# DLY_1_0.net
KiCad netlist of a schematic drawn in EAGLE
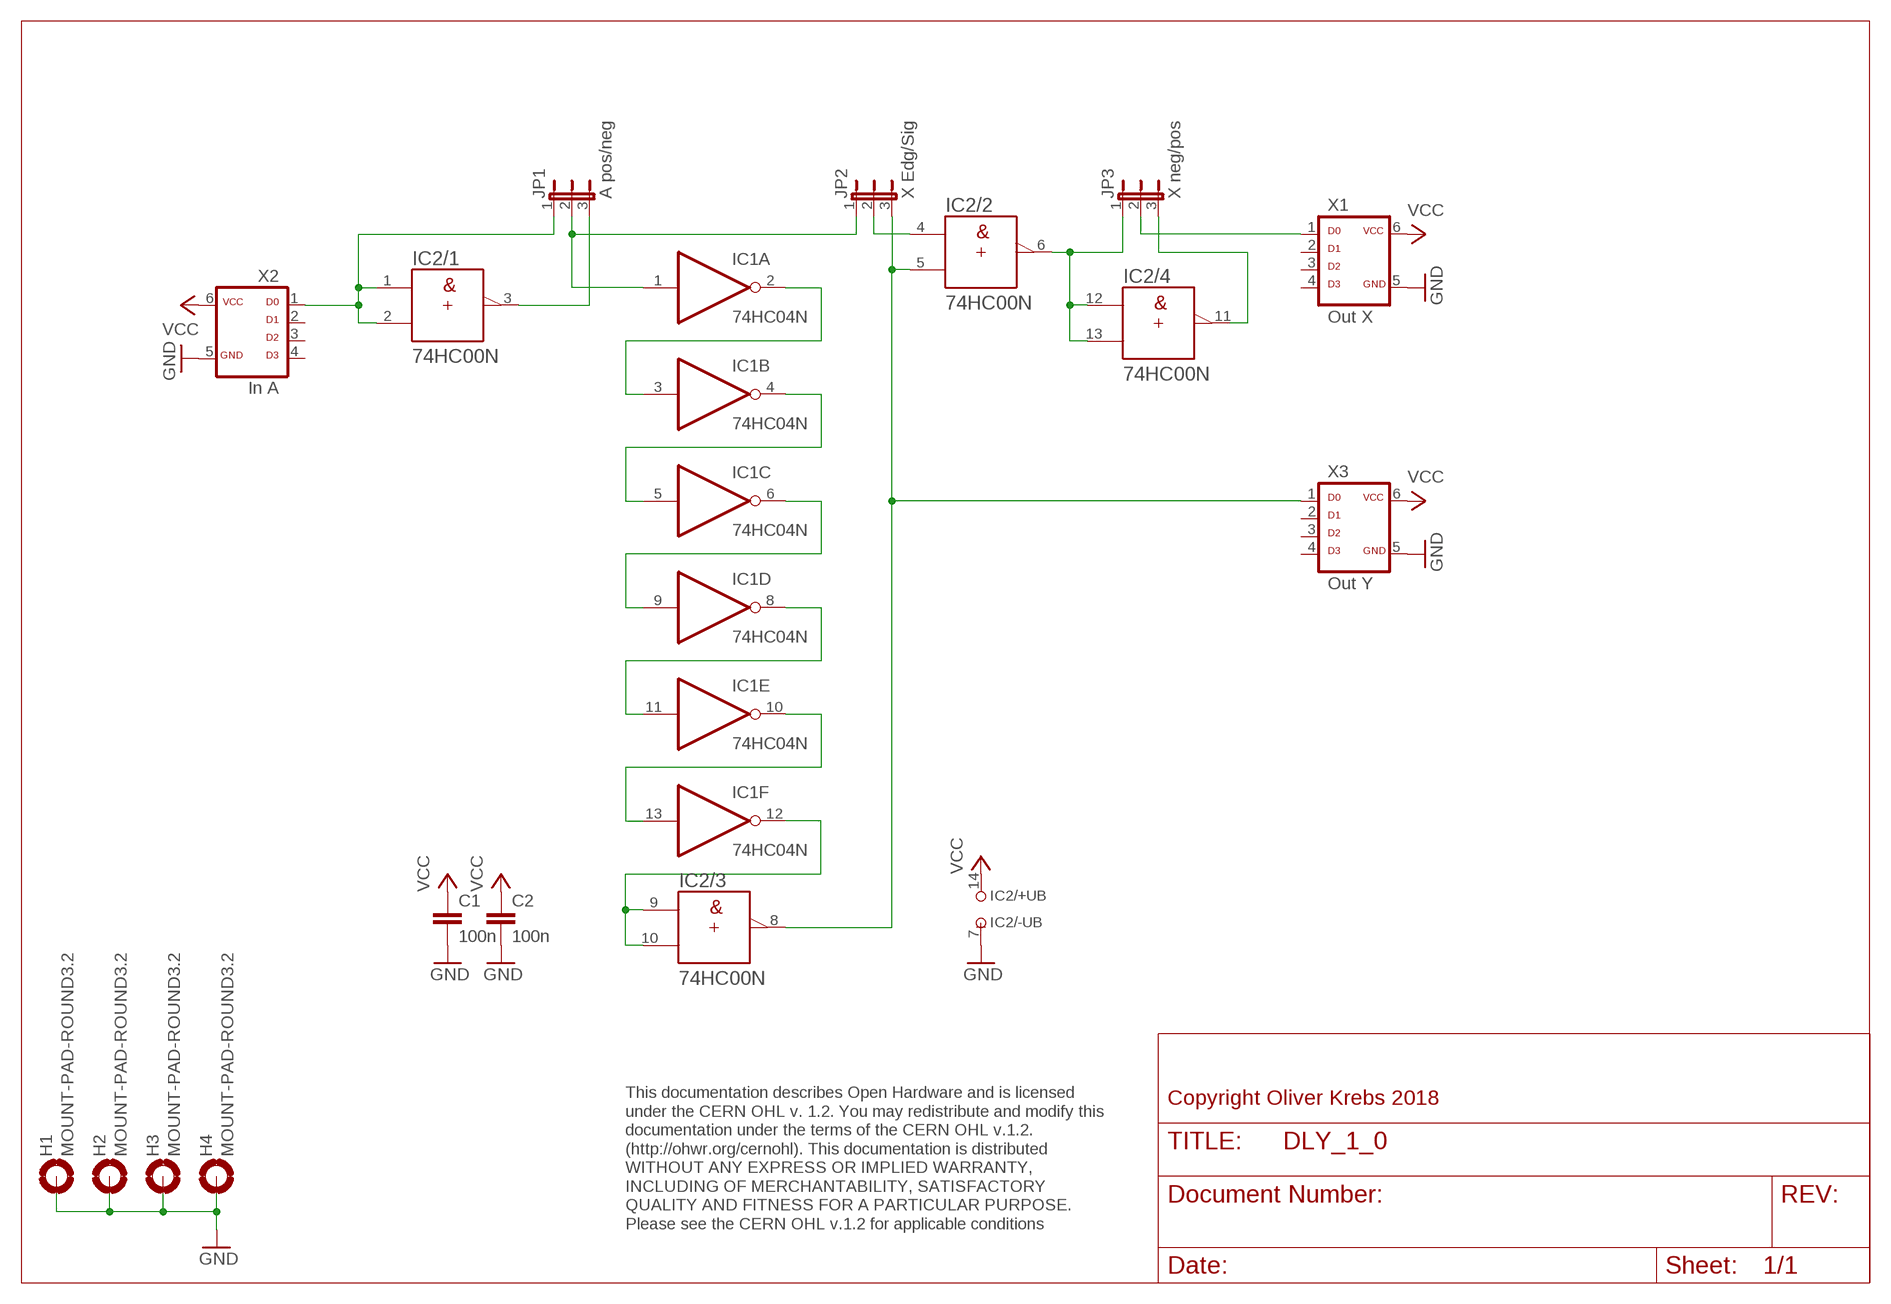
[diagram p0: schematic, sheet 1]

(export (version "E")
  (design (tool "Eeschema 10.0.6"))
  (components
    (comp (ref "C1")
      (value "100n")
      (footprint "eagle-import:C050-025X075")
      (libsource (lib "eagle-import") (part "C-EU050-025X075"))
    )
    (comp (ref "C2")
      (value "100n")
      (footprint "eagle-import:C050-025X075")
      (libsource (lib "eagle-import") (part "C-EU050-025X075"))
    )
    (comp (ref "H1")
      (value "MOUNT-PAD-ROUND3.2")
      (footprint "eagle-import:3,2-PAD")
      (libsource (lib "eagle-import") (part "MOUNT-PAD-ROUND3.2"))
    )
    (comp (ref "H2")
      (value "MOUNT-PAD-ROUND3.2")
      (footprint "eagle-import:3,2-PAD")
      (libsource (lib "eagle-import") (part "MOUNT-PAD-ROUND3.2"))
    )
    (comp (ref "H3")
      (value "MOUNT-PAD-ROUND3.2")
      (footprint "eagle-import:3,2-PAD")
      (libsource (lib "eagle-import") (part "MOUNT-PAD-ROUND3.2"))
    )
    (comp (ref "H4")
      (value "MOUNT-PAD-ROUND3.2")
      (footprint "eagle-import:3,2-PAD")
      (libsource (lib "eagle-import") (part "MOUNT-PAD-ROUND3.2"))
    )
    (comp (ref "IC1")
      (value "74HC04N")
      (footprint "eagle-import:DIL14")
      (libsource (lib "eagle-import") (part "7404NHC"))
    )
    (comp (ref "IC2")
      (value "74HC00N")
      (footprint "eagle-import:DIL14")
      (libsource (lib "eagle-import") (part "7400NHC"))
    )
    (comp (ref "JP1")
      (value "A pos/neg")
      (footprint "eagle-import:JP2")
      (libsource (lib "eagle-import") (part "JP2EJP2"))
    )
    (comp (ref "JP2")
      (value "X Edg/Sig")
      (footprint "eagle-import:JP2")
      (libsource (lib "eagle-import") (part "JP2EJP2"))
    )
    (comp (ref "JP3")
      (value "X neg/pos")
      (footprint "eagle-import:JP2")
      (libsource (lib "eagle-import") (part "JP2EJP2"))
    )
    (comp (ref "X1")
      (value "Out X")
      (footprint "eagle-import:ML-6")
      (libsource (lib "eagle-import") (part "ML6D"))
    )
    (comp (ref "X2")
      (value "In A")
      (footprint "eagle-import:ML-6")
      (libsource (lib "eagle-import") (part "ML6D"))
    )
    (comp (ref "X3")
      (value "Out Y")
      (footprint "eagle-import:ML-6")
      (libsource (lib "eagle-import") (part "ML6D"))
    )
  )
  (nets
    (net (code "1") (name "GND") (class "Default")
      (node (ref "C1") (pin "2") (pinfunction "2_2") (pintype "passive"))
      (node (ref "C2") (pin "2") (pinfunction "2_2") (pintype "passive"))
      (node (ref "H1") (pin "B3,2") (pinfunction "MOUNT_B3,2") (pintype "passive"))
      (node (ref "H2") (pin "B3,2") (pinfunction "MOUNT_B3,2") (pintype "passive"))
      (node (ref "H3") (pin "B3,2") (pinfunction "MOUNT_B3,2") (pintype "passive"))
      (node (ref "H4") (pin "B3,2") (pinfunction "MOUNT_B3,2") (pintype "passive"))
      (node (ref "IC2") (pin "7") (pinfunction "-UB_7") (pintype "power_in"))
      (node (ref "X1") (pin "5") (pinfunction "5_5") (pintype "passive"))
      (node (ref "X2") (pin "5") (pinfunction "5_5") (pintype "passive"))
      (node (ref "X3") (pin "5") (pinfunction "5_5") (pintype "passive"))
    )
    (net (code "2") (name "Net-(IC1A-I)") (class "Default")
      (node (ref "IC1") (pin "1") (pinfunction "I_1") (pintype "input"))
      (node (ref "JP1") (pin "2") (pinfunction "2_2") (pintype "passive"))
      (node (ref "JP2") (pin "1") (pinfunction "1_1") (pintype "passive"))
    )
    (net (code "3") (name "Net-(IC1A-O)") (class "Default")
      (node (ref "IC1") (pin "2") (pinfunction "O_2") (pintype "output"))
      (node (ref "IC1") (pin "3") (pinfunction "I_3") (pintype "input"))
    )
    (net (code "4") (name "Net-(IC1B-O)") (class "Default")
      (node (ref "IC1") (pin "4") (pinfunction "O_4") (pintype "output"))
      (node (ref "IC1") (pin "5") (pinfunction "I_5") (pintype "input"))
    )
    (net (code "5") (name "Net-(IC1C-O)") (class "Default")
      (node (ref "IC1") (pin "6") (pinfunction "O_6") (pintype "output"))
      (node (ref "IC1") (pin "9") (pinfunction "I_9") (pintype "input"))
    )
    (net (code "6") (name "Net-(IC1D-O)") (class "Default")
      (node (ref "IC1") (pin "11") (pinfunction "I_11") (pintype "input"))
      (node (ref "IC1") (pin "8") (pinfunction "O_8") (pintype "output"))
    )
    (net (code "7") (name "Net-(IC1E-O)") (class "Default")
      (node (ref "IC1") (pin "10") (pinfunction "O_10") (pintype "output"))
      (node (ref "IC1") (pin "13") (pinfunction "I_13") (pintype "input"))
    )
    (net (code "8") (name "Net-(IC1F-O)") (class "Default")
      (node (ref "IC1") (pin "12") (pinfunction "O_12") (pintype "output"))
      (node (ref "IC2") (pin "10") (pinfunction "B_10") (pintype "input"))
      (node (ref "IC2") (pin "9") (pinfunction "A_9") (pintype "input"))
    )
    (net (code "9") (name "Net-(IC2C-A)") (class "Default")
      (node (ref "IC2") (pin "1") (pinfunction "A_1") (pintype "input"))
      (node (ref "IC2") (pin "2") (pinfunction "B_2") (pintype "input"))
      (node (ref "JP1") (pin "1") (pinfunction "1_1") (pintype "passive"))
      (node (ref "X2") (pin "1") (pinfunction "1_1") (pintype "passive"))
    )
    (net (code "10") (name "Net-(IC2C-Y)") (class "Default")
      (node (ref "IC2") (pin "3") (pinfunction "Y_3") (pintype "output"))
      (node (ref "JP1") (pin "3") (pinfunction "3_3") (pintype "passive"))
    )
    (net (code "11") (name "Net-(IC2D-A)") (class "Default")
      (node (ref "IC2") (pin "4") (pinfunction "A_4") (pintype "input"))
      (node (ref "JP2") (pin "2") (pinfunction "2_2") (pintype "passive"))
    )
    (net (code "12") (name "Net-(IC2D-B)") (class "Default")
      (node (ref "IC2") (pin "5") (pinfunction "B_5") (pintype "input"))
      (node (ref "IC2") (pin "8") (pinfunction "Y_8") (pintype "output"))
      (node (ref "JP2") (pin "3") (pinfunction "3_3") (pintype "passive"))
      (node (ref "X3") (pin "1") (pinfunction "1_1") (pintype "passive"))
    )
    (net (code "13") (name "Net-(IC2D-Y)") (class "Default")
      (node (ref "IC2") (pin "12") (pinfunction "A_12") (pintype "input"))
      (node (ref "IC2") (pin "13") (pinfunction "B_13") (pintype "input"))
      (node (ref "IC2") (pin "6") (pinfunction "Y_6") (pintype "output"))
      (node (ref "JP3") (pin "1") (pinfunction "1_1") (pintype "passive"))
    )
    (net (code "14") (name "Net-(IC2F-Y)") (class "Default")
      (node (ref "IC2") (pin "11") (pinfunction "Y_11") (pintype "output"))
      (node (ref "JP3") (pin "3") (pinfunction "3_3") (pintype "passive"))
    )
    (net (code "15") (name "Net-(JP3-Pad2)") (class "Default")
      (node (ref "JP3") (pin "2") (pinfunction "2_2") (pintype "passive"))
      (node (ref "X1") (pin "1") (pinfunction "1_1") (pintype "passive"))
    )
    (net (code "16") (name "VCC") (class "Default")
      (node (ref "C1") (pin "1") (pinfunction "1_1") (pintype "passive"))
      (node (ref "C2") (pin "1") (pinfunction "1_1") (pintype "passive"))
      (node (ref "IC2") (pin "14") (pinfunction "+UB_14") (pintype "power_in"))
      (node (ref "X1") (pin "6") (pinfunction "6_6") (pintype "passive"))
      (node (ref "X2") (pin "6") (pinfunction "6_6") (pintype "passive"))
      (node (ref "X3") (pin "6") (pinfunction "6_6") (pintype "passive"))
    )
    (net (code "17") (name "unconnected-(X1-Pad2)") (class "Default")
      (node (ref "X1") (pin "2") (pinfunction "2_2") (pintype "passive"))
    )
    (net (code "18") (name "unconnected-(X1-Pad3)") (class "Default")
      (node (ref "X1") (pin "3") (pinfunction "3_3") (pintype "passive"))
    )
    (net (code "19") (name "unconnected-(X1-Pad4)") (class "Default")
      (node (ref "X1") (pin "4") (pinfunction "4_4") (pintype "passive"))
    )
    (net (code "20") (name "unconnected-(X2-Pad2)") (class "Default")
      (node (ref "X2") (pin "2") (pinfunction "2_2") (pintype "passive"))
    )
    (net (code "21") (name "unconnected-(X2-Pad3)") (class "Default")
      (node (ref "X2") (pin "3") (pinfunction "3_3") (pintype "passive"))
    )
    (net (code "22") (name "unconnected-(X2-Pad4)") (class "Default")
      (node (ref "X2") (pin "4") (pinfunction "4_4") (pintype "passive"))
    )
    (net (code "23") (name "unconnected-(X3-Pad2)") (class "Default")
      (node (ref "X3") (pin "2") (pinfunction "2_2") (pintype "passive"))
    )
    (net (code "24") (name "unconnected-(X3-Pad3)") (class "Default")
      (node (ref "X3") (pin "3") (pinfunction "3_3") (pintype "passive"))
    )
    (net (code "25") (name "unconnected-(X3-Pad4)") (class "Default")
      (node (ref "X3") (pin "4") (pinfunction "4_4") (pintype "passive"))
    )
  )
)
